# emru_nano.net
KiCad netlist of a schematic drawn in EAGLE
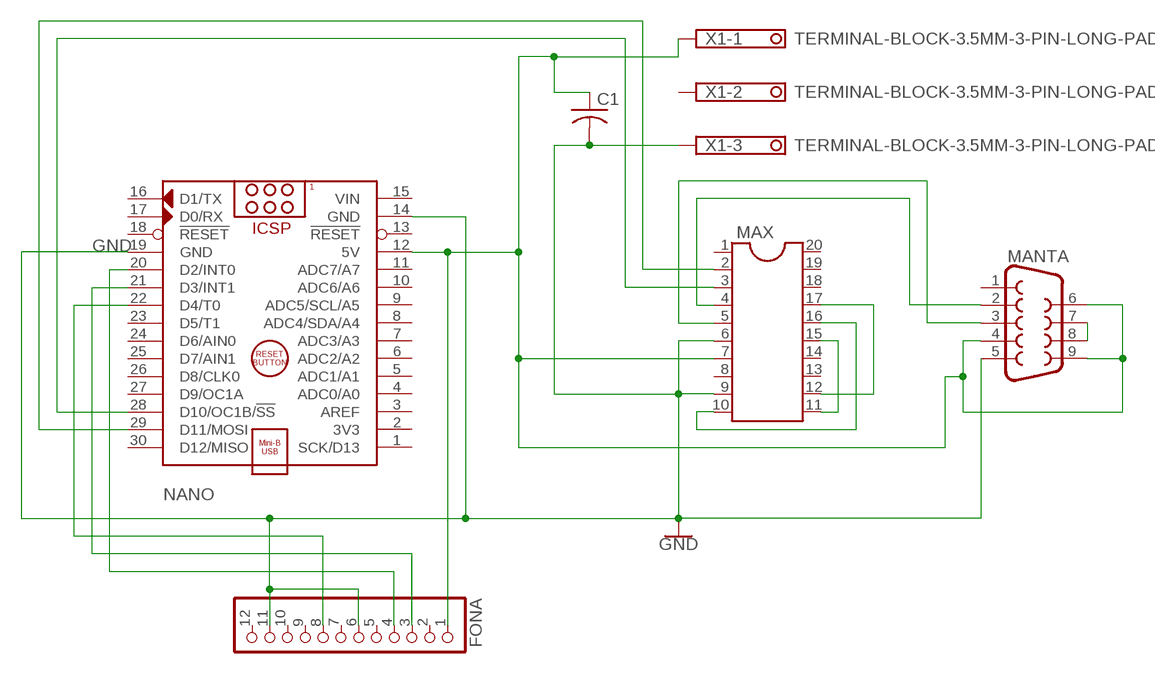
[diagram p0: schematic, sheet 1]

(export (version "E")
  (design (tool "Eeschema 10.0.6"))
  (components
    (comp (ref "C1")
      (value "C-US025-025X050")
      (footprint "eagle-import:C025-025X050")
      (libsource (lib "eagle-import") (part "C-US025-025X050"))
    )
    (comp (ref "FONA")
      (value "PINHD-1X12")
      (footprint "eagle-import:1X12")
      (libsource (lib "eagle-import") (part "PINHD-1X12"))
    )
    (comp (ref "MANTA")
      (value "DB9MALE")
      (footprint "eagle-import:DB9_MALE")
      (libsource (lib "eagle-import") (part "DB9MALE"))
    )
    (comp (ref "MAX")
      (value "DIL20")
      (footprint "eagle-import:DIL20")
      (libsource (lib "eagle-import") (part "DIL20"))
    )
    (comp (ref "NANO")
      (value "ARDUINO_NANO")
      (footprint "eagle-import:ARDUINO_NANO")
      (libsource (lib "eagle-import") (part "ARDUINO_NANO"))
    )
    (comp (ref "X1")
      (value "TERMINAL-BLOCK-3.5MM-3-PIN-LONG-PAD")
      (footprint "eagle-import:TERMINAL-BLOCK-3-PIN-3.5MM-LONG-PAD")
      (libsource (lib "eagle-import") (part "TERMINAL-BLOCK-3.5MM-3-PIN-LONG-PAD"))
    )
  )
  (nets
    (net (code "1") (name "/VIN") (class "Default")
      (node (ref "NANO") (pin "15") (pinfunction "VIN_15") (pintype "power_in"))
    )
    (net (code "2") (name "GND") (class "Default")
      (node (ref "C1") (pin "2") (pinfunction "2_2") (pintype "passive"))
      (node (ref "FONA") (pin "11") (pinfunction "11_11") (pintype "passive"))
      (node (ref "FONA") (pin "6") (pinfunction "6_6") (pintype "passive"))
      (node (ref "MANTA") (pin "5") (pinfunction "5_5") (pintype "passive"))
      (node (ref "MAX") (pin "6") (pinfunction "6_6") (pintype "passive"))
      (node (ref "MAX") (pin "9") (pinfunction "9_9") (pintype "passive"))
      (node (ref "NANO") (pin "14") (pinfunction "GND_14") (pintype "power_in"))
      (node (ref "NANO") (pin "19") (pinfunction "GND_19") (pintype "power_in"))
      (node (ref "X1") (pin "3") (pinfunction "K_3") (pintype "passive"))
    )
    (net (code "3") (name "Net-(MANTA-Pad2)") (class "Default")
      (node (ref "MANTA") (pin "2") (pinfunction "2_2") (pintype "passive"))
      (node (ref "MAX") (pin "4") (pinfunction "4_4") (pintype "passive"))
    )
    (net (code "4") (name "Net-(MANTA-Pad3)") (class "Default")
      (node (ref "MANTA") (pin "3") (pinfunction "3_3") (pintype "passive"))
      (node (ref "MAX") (pin "5") (pinfunction "5_5") (pintype "passive"))
    )
    (net (code "5") (name "Net-(MANTA-Pad7)") (class "Default")
      (node (ref "MANTA") (pin "7") (pinfunction "7_7") (pintype "passive"))
      (node (ref "MANTA") (pin "8") (pinfunction "8_8") (pintype "passive"))
    )
    (net (code "6") (name "Net-(MAX-Pad10)") (class "Default")
      (node (ref "MAX") (pin "10") (pinfunction "10_10") (pintype "passive"))
      (node (ref "MAX") (pin "16") (pinfunction "16_16") (pintype "passive"))
    )
    (net (code "7") (name "Net-(MAX-Pad11)") (class "Default")
      (node (ref "MAX") (pin "11") (pinfunction "11_11") (pintype "passive"))
      (node (ref "MAX") (pin "15") (pinfunction "15_15") (pintype "passive"))
    )
    (net (code "8") (name "Net-(MAX-Pad12)") (class "Default")
      (node (ref "MAX") (pin "12") (pinfunction "12_12") (pintype "passive"))
      (node (ref "MAX") (pin "17") (pinfunction "17_17") (pintype "passive"))
    )
    (net (code "9") (name "Net-(NANO-5V)") (class "Default")
      (node (ref "C1") (pin "1") (pinfunction "1_1") (pintype "passive"))
      (node (ref "FONA") (pin "1") (pinfunction "1_1") (pintype "passive"))
      (node (ref "MANTA") (pin "4") (pinfunction "4_4") (pintype "passive"))
      (node (ref "MANTA") (pin "6") (pinfunction "6_6") (pintype "passive"))
      (node (ref "MANTA") (pin "9") (pinfunction "9_9") (pintype "passive"))
      (node (ref "MAX") (pin "7") (pinfunction "7_7") (pintype "passive"))
      (node (ref "NANO") (pin "12") (pinfunction "5V_12") (pintype "power_in"))
      (node (ref "X1") (pin "1") (pinfunction "K_1") (pintype "passive"))
    )
    (net (code "10") (name "Net-(NANO-D2{slash}INT0)") (class "Default")
      (node (ref "FONA") (pin "4") (pinfunction "4_4") (pintype "passive"))
      (node (ref "NANO") (pin "20") (pinfunction "D2/INT0_20") (pintype "bidirectional"))
    )
    (net (code "11") (name "Net-(NANO-D3{slash}INT1)") (class "Default")
      (node (ref "FONA") (pin "3") (pinfunction "3_3") (pintype "passive"))
      (node (ref "NANO") (pin "21") (pinfunction "D3/INT1_21") (pintype "bidirectional"))
    )
    (net (code "12") (name "Net-(NANO-D4{slash}T0)") (class "Default")
      (node (ref "FONA") (pin "8") (pinfunction "8_8") (pintype "passive"))
      (node (ref "NANO") (pin "22") (pinfunction "D4/T0_22") (pintype "bidirectional"))
    )
    (net (code "13") (name "Net-(NANO-D10{slash}OC1B{slash}~{SS})") (class "Default")
      (node (ref "MAX") (pin "3") (pinfunction "3_3") (pintype "passive"))
      (node (ref "NANO") (pin "28") (pinfunction "D10/OC1B/~{SS}_28") (pintype "bidirectional"))
    )
    (net (code "14") (name "Net-(NANO-D11{slash}MOSI)") (class "Default")
      (node (ref "MAX") (pin "2") (pinfunction "2_2") (pintype "passive"))
      (node (ref "NANO") (pin "29") (pinfunction "D11/MOSI_29") (pintype "bidirectional"))
    )
    (net (code "15") (name "unconnected-(FONA-Pad2)") (class "Default")
      (node (ref "FONA") (pin "2") (pinfunction "2_2") (pintype "passive"))
    )
    (net (code "16") (name "unconnected-(FONA-Pad5)") (class "Default")
      (node (ref "FONA") (pin "5") (pinfunction "5_5") (pintype "passive"))
    )
    (net (code "17") (name "unconnected-(FONA-Pad7)") (class "Default")
      (node (ref "FONA") (pin "7") (pinfunction "7_7") (pintype "passive"))
    )
    (net (code "18") (name "unconnected-(FONA-Pad9)") (class "Default")
      (node (ref "FONA") (pin "9") (pinfunction "9_9") (pintype "passive"))
    )
    (net (code "19") (name "unconnected-(FONA-Pad10)") (class "Default")
      (node (ref "FONA") (pin "10") (pinfunction "10_10") (pintype "passive"))
    )
    (net (code "20") (name "unconnected-(FONA-Pad12)") (class "Default")
      (node (ref "FONA") (pin "12") (pinfunction "12_12") (pintype "passive"))
    )
    (net (code "21") (name "unconnected-(MANTA-Pad1)") (class "Default")
      (node (ref "MANTA") (pin "1") (pinfunction "1_1") (pintype "passive"))
    )
    (net (code "22") (name "unconnected-(MAX-Pad1)") (class "Default")
      (node (ref "MAX") (pin "1") (pinfunction "1_1") (pintype "passive"))
    )
    (net (code "23") (name "unconnected-(MAX-Pad8)") (class "Default")
      (node (ref "MAX") (pin "8") (pinfunction "8_8") (pintype "passive"))
    )
    (net (code "24") (name "unconnected-(MAX-Pad13)") (class "Default")
      (node (ref "MAX") (pin "13") (pinfunction "13_13") (pintype "passive"))
    )
    (net (code "25") (name "unconnected-(MAX-Pad14)") (class "Default")
      (node (ref "MAX") (pin "14") (pinfunction "14_14") (pintype "passive"))
    )
    (net (code "26") (name "unconnected-(MAX-Pad18)") (class "Default")
      (node (ref "MAX") (pin "18") (pinfunction "18_18") (pintype "passive"))
    )
    (net (code "27") (name "unconnected-(MAX-Pad19)") (class "Default")
      (node (ref "MAX") (pin "19") (pinfunction "19_19") (pintype "passive"))
    )
    (net (code "28") (name "unconnected-(MAX-Pad20)") (class "Default")
      (node (ref "MAX") (pin "20") (pinfunction "20_20") (pintype "passive"))
    )
    (net (code "29") (name "unconnected-(NANO-3V3-Pad2)") (class "Default")
      (node (ref "NANO") (pin "2") (pinfunction "3V3_2") (pintype "output"))
    )
    (net (code "30") (name "unconnected-(NANO-ADC0{slash}A0-Pad4)") (class "Default")
      (node (ref "NANO") (pin "4") (pinfunction "ADC0/A0_4") (pintype "bidirectional"))
    )
    (net (code "31") (name "unconnected-(NANO-ADC1{slash}A1-Pad5)") (class "Default")
      (node (ref "NANO") (pin "5") (pinfunction "ADC1/A1_5") (pintype "bidirectional"))
    )
    (net (code "32") (name "unconnected-(NANO-ADC2{slash}A2-Pad6)") (class "Default")
      (node (ref "NANO") (pin "6") (pinfunction "ADC2/A2_6") (pintype "bidirectional"))
    )
    (net (code "33") (name "unconnected-(NANO-ADC3{slash}A3-Pad7)") (class "Default")
      (node (ref "NANO") (pin "7") (pinfunction "ADC3/A3_7") (pintype "bidirectional"))
    )
    (net (code "34") (name "unconnected-(NANO-ADC4{slash}SDA{slash}A4-Pad8)") (class "Default")
      (node (ref "NANO") (pin "8") (pinfunction "ADC4/SDA/A4_8") (pintype "bidirectional"))
    )
    (net (code "35") (name "unconnected-(NANO-ADC5{slash}SCL{slash}A5-Pad9)") (class "Default")
      (node (ref "NANO") (pin "9") (pinfunction "ADC5/SCL/A5_9") (pintype "bidirectional"))
    )
    (net (code "36") (name "unconnected-(NANO-ADC6{slash}A6-Pad10)") (class "Default")
      (node (ref "NANO") (pin "10") (pinfunction "ADC6/A6_10") (pintype "bidirectional"))
    )
    (net (code "37") (name "unconnected-(NANO-ADC7{slash}A7-Pad11)") (class "Default")
      (node (ref "NANO") (pin "11") (pinfunction "ADC7/A7_11") (pintype "bidirectional"))
    )
    (net (code "38") (name "unconnected-(NANO-AREF-Pad3)") (class "Default")
      (node (ref "NANO") (pin "3") (pinfunction "AREF_3") (pintype "input"))
    )
    (net (code "39") (name "unconnected-(NANO-D0{slash}RX-Pad17)") (class "Default")
      (node (ref "NANO") (pin "17") (pinfunction "D0/RX_17") (pintype "bidirectional"))
    )
    (net (code "40") (name "unconnected-(NANO-D1{slash}TX-Pad16)") (class "Default")
      (node (ref "NANO") (pin "16") (pinfunction "D1/TX_16") (pintype "bidirectional"))
    )
    (net (code "41") (name "unconnected-(NANO-D5{slash}T1-Pad23)") (class "Default")
      (node (ref "NANO") (pin "23") (pinfunction "D5/T1_23") (pintype "bidirectional"))
    )
    (net (code "42") (name "unconnected-(NANO-D6{slash}AIN0-Pad24)") (class "Default")
      (node (ref "NANO") (pin "24") (pinfunction "D6/AIN0_24") (pintype "bidirectional"))
    )
    (net (code "43") (name "unconnected-(NANO-D7{slash}AIN1-Pad25)") (class "Default")
      (node (ref "NANO") (pin "25") (pinfunction "D7/AIN1_25") (pintype "bidirectional"))
    )
    (net (code "44") (name "unconnected-(NANO-D8{slash}CLK0-Pad26)") (class "Default")
      (node (ref "NANO") (pin "26") (pinfunction "D8/CLK0_26") (pintype "bidirectional"))
    )
    (net (code "45") (name "unconnected-(NANO-D9{slash}OC1A-Pad27)") (class "Default")
      (node (ref "NANO") (pin "27") (pinfunction "D9/OC1A_27") (pintype "bidirectional"))
    )
    (net (code "46") (name "unconnected-(NANO-D12{slash}MISO-Pad30)") (class "Default")
      (node (ref "NANO") (pin "30") (pinfunction "D12/MISO_30") (pintype "bidirectional"))
    )
    (net (code "47") (name "unconnected-(NANO-SCK{slash}D13-Pad1)") (class "Default")
      (node (ref "NANO") (pin "1") (pinfunction "SCK/D13_1") (pintype "bidirectional"))
    )
    (net (code "48") (name "unconnected-(NANO-~{RESET}-Pad13)") (class "Default")
      (node (ref "NANO") (pin "13") (pinfunction "~{RESET}_13") (pintype "input"))
    )
    (net (code "49") (name "unconnected-(NANO-~{RESET}-Pad18)") (class "Default")
      (node (ref "NANO") (pin "18") (pinfunction "~{RESET}_18") (pintype "input"))
    )
    (net (code "50") (name "unconnected-(X1B-K-Pad2)") (class "Default")
      (node (ref "X1") (pin "2") (pinfunction "K_2") (pintype "passive"))
    )
  )
)
